# large_led_ring.net
KiCad netlist of a schematic drawn in EAGLE
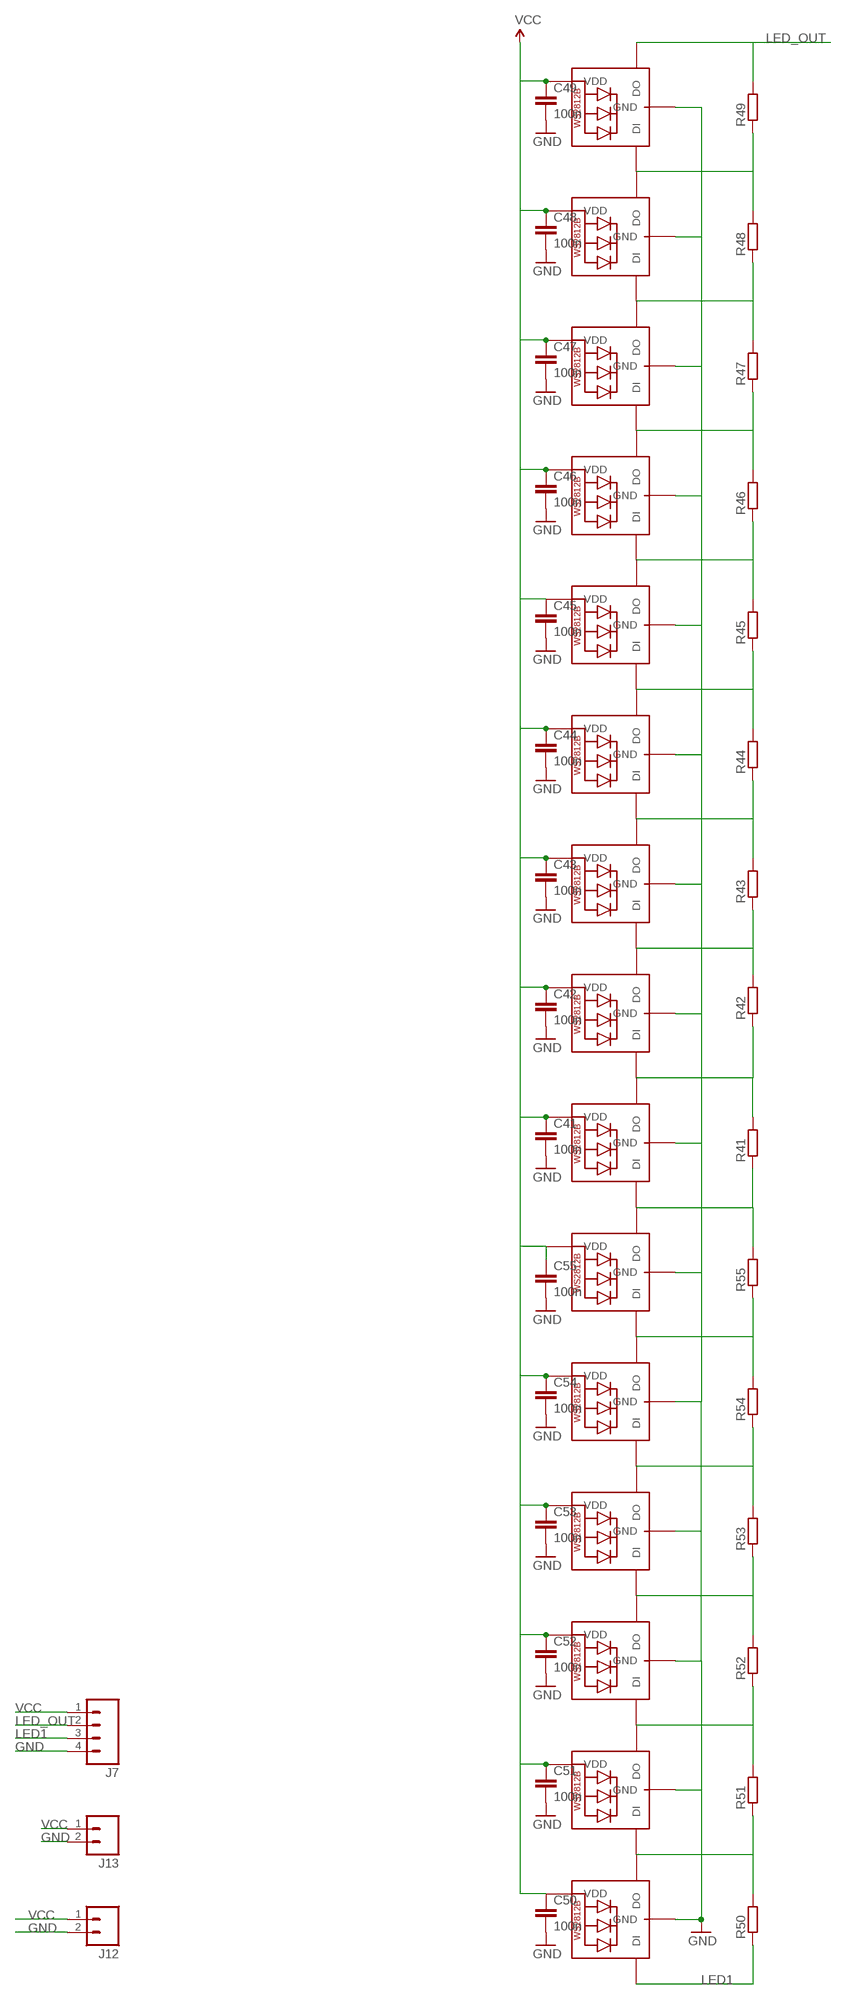
[diagram p0: schematic, sheet 1]

(export (version "E")
  (design (tool "Eeschema 10.0.6"))
  (components
    (comp (ref "C41")
      (value "100n")
      (footprint "eagle-import:0603-CAP")
      (libsource (lib "eagle-import") (part "CAP0603-CAP"))
    )
    (comp (ref "C42")
      (value "100n")
      (footprint "eagle-import:0603-CAP")
      (libsource (lib "eagle-import") (part "CAP0603-CAP"))
    )
    (comp (ref "C43")
      (value "100n")
      (footprint "eagle-import:0603-CAP")
      (libsource (lib "eagle-import") (part "CAP0603-CAP"))
    )
    (comp (ref "C44")
      (value "100n")
      (footprint "eagle-import:0603-CAP")
      (libsource (lib "eagle-import") (part "CAP0603-CAP"))
    )
    (comp (ref "C45")
      (value "100n")
      (footprint "eagle-import:0603-CAP")
      (libsource (lib "eagle-import") (part "CAP0603-CAP"))
    )
    (comp (ref "C46")
      (value "100n")
      (footprint "eagle-import:0603-CAP")
      (libsource (lib "eagle-import") (part "CAP0603-CAP"))
    )
    (comp (ref "C47")
      (value "100n")
      (footprint "eagle-import:0603-CAP")
      (libsource (lib "eagle-import") (part "CAP0603-CAP"))
    )
    (comp (ref "C48")
      (value "100n")
      (footprint "eagle-import:0603-CAP")
      (libsource (lib "eagle-import") (part "CAP0603-CAP"))
    )
    (comp (ref "C49")
      (value "100n")
      (footprint "eagle-import:0603-CAP")
      (libsource (lib "eagle-import") (part "CAP0603-CAP"))
    )
    (comp (ref "C50")
      (value "100n")
      (footprint "eagle-import:0603-CAP")
      (libsource (lib "eagle-import") (part "CAP0603-CAP"))
    )
    (comp (ref "C51")
      (value "100n")
      (footprint "eagle-import:0603-CAP")
      (libsource (lib "eagle-import") (part "CAP0603-CAP"))
    )
    (comp (ref "C52")
      (value "100n")
      (footprint "eagle-import:0603-CAP")
      (libsource (lib "eagle-import") (part "CAP0603-CAP"))
    )
    (comp (ref "C53")
      (value "100n")
      (footprint "eagle-import:0603-CAP")
      (libsource (lib "eagle-import") (part "CAP0603-CAP"))
    )
    (comp (ref "C54")
      (value "100n")
      (footprint "eagle-import:0603-CAP")
      (libsource (lib "eagle-import") (part "CAP0603-CAP"))
    )
    (comp (ref "C55")
      (value "100n")
      (footprint "eagle-import:0603-CAP")
      (libsource (lib "eagle-import") (part "CAP0603-CAP"))
    )
    (comp (ref "J7")
      (value "M04NO_SILK_ALL_ROUND")
      (footprint "eagle-import:1X04_NO_SILK_ALL_ROUND")
      (libsource (lib "eagle-import") (part "M04NO_SILK_ALL_ROUND"))
    )
    (comp (ref "J12")
      (value "M021X02_NO_SILK")
      (footprint "eagle-import:1X02_NO_SILK")
      (libsource (lib "eagle-import") (part "M021X02_NO_SILK"))
    )
    (comp (ref "J13")
      (value "M021X02_NO_SILK")
      (footprint "eagle-import:1X02_NO_SILK")
      (libsource (lib "eagle-import") (part "M021X02_NO_SILK"))
    )
    (comp (ref "LED31")
      (value "WS2812B3535")
      (footprint "eagle-import:LED3535")
      (libsource (lib "eagle-import") (part "WS2812B3535"))
    )
    (comp (ref "LED32")
      (value "WS2812B3535")
      (footprint "eagle-import:LED3535")
      (libsource (lib "eagle-import") (part "WS2812B3535"))
    )
    (comp (ref "LED33")
      (value "WS2812B3535")
      (footprint "eagle-import:LED3535")
      (libsource (lib "eagle-import") (part "WS2812B3535"))
    )
    (comp (ref "LED34")
      (value "WS2812B3535")
      (footprint "eagle-import:LED3535")
      (libsource (lib "eagle-import") (part "WS2812B3535"))
    )
    (comp (ref "LED35")
      (value "WS2812B3535")
      (footprint "eagle-import:LED3535")
      (libsource (lib "eagle-import") (part "WS2812B3535"))
    )
    (comp (ref "LED36")
      (value "WS2812B3535")
      (footprint "eagle-import:LED3535")
      (libsource (lib "eagle-import") (part "WS2812B3535"))
    )
    (comp (ref "LED37")
      (value "WS2812B3535")
      (footprint "eagle-import:LED3535")
      (libsource (lib "eagle-import") (part "WS2812B3535"))
    )
    (comp (ref "LED38")
      (value "WS2812B3535")
      (footprint "eagle-import:LED3535")
      (libsource (lib "eagle-import") (part "WS2812B3535"))
    )
    (comp (ref "LED39")
      (value "WS2812B3535")
      (footprint "eagle-import:LED3535")
      (libsource (lib "eagle-import") (part "WS2812B3535"))
    )
    (comp (ref "LED40")
      (value "WS2812B3535")
      (footprint "eagle-import:LED3535")
      (libsource (lib "eagle-import") (part "WS2812B3535"))
    )
    (comp (ref "LED41")
      (value "WS2812B3535")
      (footprint "eagle-import:LED3535")
      (libsource (lib "eagle-import") (part "WS2812B3535"))
    )
    (comp (ref "LED42")
      (value "WS2812B3535")
      (footprint "eagle-import:LED3535")
      (libsource (lib "eagle-import") (part "WS2812B3535"))
    )
    (comp (ref "LED43")
      (value "WS2812B3535")
      (footprint "eagle-import:LED3535")
      (libsource (lib "eagle-import") (part "WS2812B3535"))
    )
    (comp (ref "LED44")
      (value "WS2812B3535")
      (footprint "eagle-import:LED3535")
      (libsource (lib "eagle-import") (part "WS2812B3535"))
    )
    (comp (ref "LED45")
      (value "WS2812B3535")
      (footprint "eagle-import:LED3535")
      (libsource (lib "eagle-import") (part "WS2812B3535"))
    )
    (comp (ref "R41")
      (value "R-EU_R0603")
      (footprint "eagle-import:R0603")
      (libsource (lib "eagle-import") (part "R-EU_R0603"))
    )
    (comp (ref "R42")
      (value "R-EU_R0603")
      (footprint "eagle-import:R0603")
      (libsource (lib "eagle-import") (part "R-EU_R0603"))
    )
    (comp (ref "R43")
      (value "R-EU_R0603")
      (footprint "eagle-import:R0603")
      (libsource (lib "eagle-import") (part "R-EU_R0603"))
    )
    (comp (ref "R44")
      (value "R-EU_R0603")
      (footprint "eagle-import:R0603")
      (libsource (lib "eagle-import") (part "R-EU_R0603"))
    )
    (comp (ref "R45")
      (value "R-EU_R0603")
      (footprint "eagle-import:R0603")
      (libsource (lib "eagle-import") (part "R-EU_R0603"))
    )
    (comp (ref "R46")
      (value "R-EU_R0603")
      (footprint "eagle-import:R0603")
      (libsource (lib "eagle-import") (part "R-EU_R0603"))
    )
    (comp (ref "R47")
      (value "R-EU_R0603")
      (footprint "eagle-import:R0603")
      (libsource (lib "eagle-import") (part "R-EU_R0603"))
    )
    (comp (ref "R48")
      (value "R-EU_R0603")
      (footprint "eagle-import:R0603")
      (libsource (lib "eagle-import") (part "R-EU_R0603"))
    )
    (comp (ref "R49")
      (value "R-EU_R0603")
      (footprint "eagle-import:R0603")
      (libsource (lib "eagle-import") (part "R-EU_R0603"))
    )
    (comp (ref "R50")
      (value "R-EU_R0603")
      (footprint "eagle-import:R0603")
      (libsource (lib "eagle-import") (part "R-EU_R0603"))
    )
    (comp (ref "R51")
      (value "R-EU_R0603")
      (footprint "eagle-import:R0603")
      (libsource (lib "eagle-import") (part "R-EU_R0603"))
    )
    (comp (ref "R52")
      (value "R-EU_R0603")
      (footprint "eagle-import:R0603")
      (libsource (lib "eagle-import") (part "R-EU_R0603"))
    )
    (comp (ref "R53")
      (value "R-EU_R0603")
      (footprint "eagle-import:R0603")
      (libsource (lib "eagle-import") (part "R-EU_R0603"))
    )
    (comp (ref "R54")
      (value "R-EU_R0603")
      (footprint "eagle-import:R0603")
      (libsource (lib "eagle-import") (part "R-EU_R0603"))
    )
    (comp (ref "R55")
      (value "R-EU_R0603")
      (footprint "eagle-import:R0603")
      (libsource (lib "eagle-import") (part "R-EU_R0603"))
    )
  )
  (nets
    (net (code "1") (name "/LED1") (class "Default")
      (node (ref "J7") (pin "3") (pinfunction "3_3") (pintype "passive"))
      (node (ref "LED31") (pin "1") (pinfunction "DI_1") (pintype "input"))
      (node (ref "R50") (pin "1") (pinfunction "1_1") (pintype "passive"))
    )
    (net (code "2") (name "/LED_OUT") (class "Default")
      (node (ref "J7") (pin "2") (pinfunction "2_2") (pintype "passive"))
      (node (ref "LED45") (pin "3") (pinfunction "DO_3") (pintype "output"))
      (node (ref "R49") (pin "2") (pinfunction "2_2") (pintype "passive"))
    )
    (net (code "3") (name "GND") (class "Default")
      (node (ref "C41") (pin "2") (pinfunction "2_2") (pintype "passive"))
      (node (ref "C42") (pin "2") (pinfunction "2_2") (pintype "passive"))
      (node (ref "C43") (pin "2") (pinfunction "2_2") (pintype "passive"))
      (node (ref "C44") (pin "2") (pinfunction "2_2") (pintype "passive"))
      (node (ref "C45") (pin "2") (pinfunction "2_2") (pintype "passive"))
      (node (ref "C46") (pin "2") (pinfunction "2_2") (pintype "passive"))
      (node (ref "C47") (pin "2") (pinfunction "2_2") (pintype "passive"))
      (node (ref "C48") (pin "2") (pinfunction "2_2") (pintype "passive"))
      (node (ref "C49") (pin "2") (pinfunction "2_2") (pintype "passive"))
      (node (ref "C50") (pin "2") (pinfunction "2_2") (pintype "passive"))
      (node (ref "C51") (pin "2") (pinfunction "2_2") (pintype "passive"))
      (node (ref "C52") (pin "2") (pinfunction "2_2") (pintype "passive"))
      (node (ref "C53") (pin "2") (pinfunction "2_2") (pintype "passive"))
      (node (ref "C54") (pin "2") (pinfunction "2_2") (pintype "passive"))
      (node (ref "C55") (pin "2") (pinfunction "2_2") (pintype "passive"))
      (node (ref "J12") (pin "2") (pinfunction "2_2") (pintype "passive"))
      (node (ref "J13") (pin "2") (pinfunction "2_2") (pintype "passive"))
      (node (ref "J7") (pin "4") (pinfunction "4_4") (pintype "passive"))
      (node (ref "LED31") (pin "4") (pinfunction "GND_4") (pintype "power_in"))
      (node (ref "LED32") (pin "4") (pinfunction "GND_4") (pintype "power_in"))
      (node (ref "LED33") (pin "4") (pinfunction "GND_4") (pintype "power_in"))
      (node (ref "LED34") (pin "4") (pinfunction "GND_4") (pintype "power_in"))
      (node (ref "LED35") (pin "4") (pinfunction "GND_4") (pintype "power_in"))
      (node (ref "LED36") (pin "4") (pinfunction "GND_4") (pintype "power_in"))
      (node (ref "LED37") (pin "4") (pinfunction "GND_4") (pintype "power_in"))
      (node (ref "LED38") (pin "4") (pinfunction "GND_4") (pintype "power_in"))
      (node (ref "LED39") (pin "4") (pinfunction "GND_4") (pintype "power_in"))
      (node (ref "LED40") (pin "4") (pinfunction "GND_4") (pintype "power_in"))
      (node (ref "LED41") (pin "4") (pinfunction "GND_4") (pintype "power_in"))
      (node (ref "LED42") (pin "4") (pinfunction "GND_4") (pintype "power_in"))
      (node (ref "LED43") (pin "4") (pinfunction "GND_4") (pintype "power_in"))
      (node (ref "LED44") (pin "4") (pinfunction "GND_4") (pintype "power_in"))
      (node (ref "LED45") (pin "4") (pinfunction "GND_4") (pintype "power_in"))
    )
    (net (code "4") (name "Net-(LED31-DO)") (class "Default")
      (node (ref "LED31") (pin "3") (pinfunction "DO_3") (pintype "output"))
      (node (ref "LED32") (pin "1") (pinfunction "DI_1") (pintype "input"))
      (node (ref "R50") (pin "2") (pinfunction "2_2") (pintype "passive"))
      (node (ref "R51") (pin "1") (pinfunction "1_1") (pintype "passive"))
    )
    (net (code "5") (name "Net-(LED32-DO)") (class "Default")
      (node (ref "LED32") (pin "3") (pinfunction "DO_3") (pintype "output"))
      (node (ref "LED33") (pin "1") (pinfunction "DI_1") (pintype "input"))
      (node (ref "R51") (pin "2") (pinfunction "2_2") (pintype "passive"))
      (node (ref "R52") (pin "1") (pinfunction "1_1") (pintype "passive"))
    )
    (net (code "6") (name "Net-(LED33-DO)") (class "Default")
      (node (ref "LED33") (pin "3") (pinfunction "DO_3") (pintype "output"))
      (node (ref "LED34") (pin "1") (pinfunction "DI_1") (pintype "input"))
      (node (ref "R52") (pin "2") (pinfunction "2_2") (pintype "passive"))
      (node (ref "R53") (pin "1") (pinfunction "1_1") (pintype "passive"))
    )
    (net (code "7") (name "Net-(LED34-DO)") (class "Default")
      (node (ref "LED34") (pin "3") (pinfunction "DO_3") (pintype "output"))
      (node (ref "LED35") (pin "1") (pinfunction "DI_1") (pintype "input"))
      (node (ref "R53") (pin "2") (pinfunction "2_2") (pintype "passive"))
      (node (ref "R54") (pin "1") (pinfunction "1_1") (pintype "passive"))
    )
    (net (code "8") (name "Net-(LED35-DO)") (class "Default")
      (node (ref "LED35") (pin "3") (pinfunction "DO_3") (pintype "output"))
      (node (ref "LED36") (pin "1") (pinfunction "DI_1") (pintype "input"))
      (node (ref "R54") (pin "2") (pinfunction "2_2") (pintype "passive"))
      (node (ref "R55") (pin "1") (pinfunction "1_1") (pintype "passive"))
    )
    (net (code "9") (name "Net-(LED36-DO)") (class "Default")
      (node (ref "LED36") (pin "3") (pinfunction "DO_3") (pintype "output"))
      (node (ref "LED37") (pin "1") (pinfunction "DI_1") (pintype "input"))
      (node (ref "R41") (pin "1") (pinfunction "1_1") (pintype "passive"))
      (node (ref "R55") (pin "2") (pinfunction "2_2") (pintype "passive"))
    )
    (net (code "10") (name "Net-(LED37-DO)") (class "Default")
      (node (ref "LED37") (pin "3") (pinfunction "DO_3") (pintype "output"))
      (node (ref "LED38") (pin "1") (pinfunction "DI_1") (pintype "input"))
      (node (ref "R41") (pin "2") (pinfunction "2_2") (pintype "passive"))
      (node (ref "R42") (pin "1") (pinfunction "1_1") (pintype "passive"))
    )
    (net (code "11") (name "Net-(LED38-DO)") (class "Default")
      (node (ref "LED38") (pin "3") (pinfunction "DO_3") (pintype "output"))
      (node (ref "LED39") (pin "1") (pinfunction "DI_1") (pintype "input"))
      (node (ref "R42") (pin "2") (pinfunction "2_2") (pintype "passive"))
      (node (ref "R43") (pin "1") (pinfunction "1_1") (pintype "passive"))
    )
    (net (code "12") (name "Net-(LED39-DO)") (class "Default")
      (node (ref "LED39") (pin "3") (pinfunction "DO_3") (pintype "output"))
      (node (ref "LED40") (pin "1") (pinfunction "DI_1") (pintype "input"))
      (node (ref "R43") (pin "2") (pinfunction "2_2") (pintype "passive"))
      (node (ref "R44") (pin "1") (pinfunction "1_1") (pintype "passive"))
    )
    (net (code "13") (name "Net-(LED40-DO)") (class "Default")
      (node (ref "LED40") (pin "3") (pinfunction "DO_3") (pintype "output"))
      (node (ref "LED41") (pin "1") (pinfunction "DI_1") (pintype "input"))
      (node (ref "R44") (pin "2") (pinfunction "2_2") (pintype "passive"))
      (node (ref "R45") (pin "1") (pinfunction "1_1") (pintype "passive"))
    )
    (net (code "14") (name "Net-(LED41-DO)") (class "Default")
      (node (ref "LED41") (pin "3") (pinfunction "DO_3") (pintype "output"))
      (node (ref "LED42") (pin "1") (pinfunction "DI_1") (pintype "input"))
      (node (ref "R45") (pin "2") (pinfunction "2_2") (pintype "passive"))
      (node (ref "R46") (pin "1") (pinfunction "1_1") (pintype "passive"))
    )
    (net (code "15") (name "Net-(LED42-DO)") (class "Default")
      (node (ref "LED42") (pin "3") (pinfunction "DO_3") (pintype "output"))
      (node (ref "LED43") (pin "1") (pinfunction "DI_1") (pintype "input"))
      (node (ref "R46") (pin "2") (pinfunction "2_2") (pintype "passive"))
      (node (ref "R47") (pin "1") (pinfunction "1_1") (pintype "passive"))
    )
    (net (code "16") (name "Net-(LED43-DO)") (class "Default")
      (node (ref "LED43") (pin "3") (pinfunction "DO_3") (pintype "output"))
      (node (ref "LED44") (pin "1") (pinfunction "DI_1") (pintype "input"))
      (node (ref "R47") (pin "2") (pinfunction "2_2") (pintype "passive"))
      (node (ref "R48") (pin "1") (pinfunction "1_1") (pintype "passive"))
    )
    (net (code "17") (name "Net-(LED44-DO)") (class "Default")
      (node (ref "LED44") (pin "3") (pinfunction "DO_3") (pintype "output"))
      (node (ref "LED45") (pin "1") (pinfunction "DI_1") (pintype "input"))
      (node (ref "R48") (pin "2") (pinfunction "2_2") (pintype "passive"))
      (node (ref "R49") (pin "1") (pinfunction "1_1") (pintype "passive"))
    )
    (net (code "18") (name "VCC") (class "Default")
      (node (ref "C41") (pin "1") (pinfunction "1_1") (pintype "passive"))
      (node (ref "C42") (pin "1") (pinfunction "1_1") (pintype "passive"))
      (node (ref "C43") (pin "1") (pinfunction "1_1") (pintype "passive"))
      (node (ref "C44") (pin "1") (pinfunction "1_1") (pintype "passive"))
      (node (ref "C45") (pin "1") (pinfunction "1_1") (pintype "passive"))
      (node (ref "C46") (pin "1") (pinfunction "1_1") (pintype "passive"))
      (node (ref "C47") (pin "1") (pinfunction "1_1") (pintype "passive"))
      (node (ref "C48") (pin "1") (pinfunction "1_1") (pintype "passive"))
      (node (ref "C49") (pin "1") (pinfunction "1_1") (pintype "passive"))
      (node (ref "C50") (pin "1") (pinfunction "1_1") (pintype "passive"))
      (node (ref "C51") (pin "1") (pinfunction "1_1") (pintype "passive"))
      (node (ref "C52") (pin "1") (pinfunction "1_1") (pintype "passive"))
      (node (ref "C53") (pin "1") (pinfunction "1_1") (pintype "passive"))
      (node (ref "C54") (pin "1") (pinfunction "1_1") (pintype "passive"))
      (node (ref "C55") (pin "1") (pinfunction "1_1") (pintype "passive"))
      (node (ref "J12") (pin "1") (pinfunction "1_1") (pintype "passive"))
      (node (ref "J13") (pin "1") (pinfunction "1_1") (pintype "passive"))
      (node (ref "J7") (pin "1") (pinfunction "1_1") (pintype "passive"))
      (node (ref "LED31") (pin "2") (pinfunction "VDD_2") (pintype "power_in"))
      (node (ref "LED32") (pin "2") (pinfunction "VDD_2") (pintype "power_in"))
      (node (ref "LED33") (pin "2") (pinfunction "VDD_2") (pintype "power_in"))
      (node (ref "LED34") (pin "2") (pinfunction "VDD_2") (pintype "power_in"))
      (node (ref "LED35") (pin "2") (pinfunction "VDD_2") (pintype "power_in"))
      (node (ref "LED36") (pin "2") (pinfunction "VDD_2") (pintype "power_in"))
      (node (ref "LED37") (pin "2") (pinfunction "VDD_2") (pintype "power_in"))
      (node (ref "LED38") (pin "2") (pinfunction "VDD_2") (pintype "power_in"))
      (node (ref "LED39") (pin "2") (pinfunction "VDD_2") (pintype "power_in"))
      (node (ref "LED40") (pin "2") (pinfunction "VDD_2") (pintype "power_in"))
      (node (ref "LED41") (pin "2") (pinfunction "VDD_2") (pintype "power_in"))
      (node (ref "LED42") (pin "2") (pinfunction "VDD_2") (pintype "power_in"))
      (node (ref "LED43") (pin "2") (pinfunction "VDD_2") (pintype "power_in"))
      (node (ref "LED44") (pin "2") (pinfunction "VDD_2") (pintype "power_in"))
      (node (ref "LED45") (pin "2") (pinfunction "VDD_2") (pintype "power_in"))
    )
  )
)
